# Rotall_Encoder_ver1_0.net
KiCad netlist of a schematic drawn in EAGLE
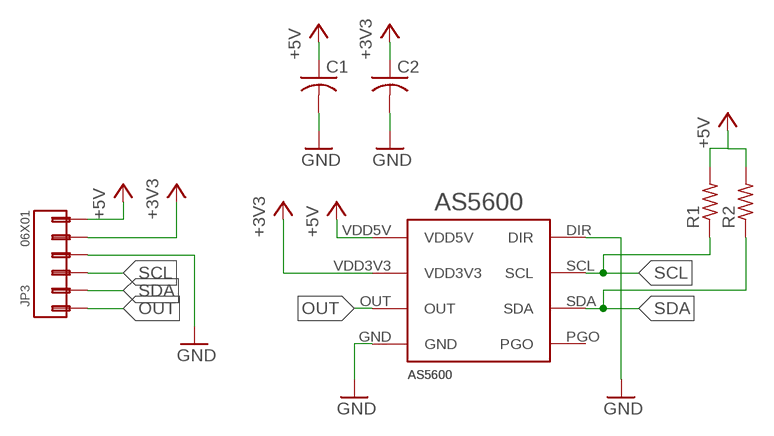
[diagram p0: schematic, sheet 1]

(export (version "E")
  (design (tool "Eeschema 10.0.6"))
  (components
    (comp (ref "C1")
      (value "C-USC0603")
      (footprint "eagle-import:C0603")
      (libsource (lib "eagle-import") (part "C-USC0603"))
    )
    (comp (ref "C2")
      (value "C-USC0603")
      (footprint "eagle-import:C0603")
      (libsource (lib "eagle-import") (part "C-USC0603"))
    )
    (comp (ref "JP3")
      (value "06X01")
      (footprint "eagle-import:06X01")
      (libsource (lib "eagle-import") (part "06X01"))
    )
    (comp (ref "R1")
      (value "R-US_R0603")
      (footprint "eagle-import:R0603")
      (libsource (lib "eagle-import") (part "R-US_R0603"))
    )
    (comp (ref "R2")
      (value "R-US_R0603")
      (footprint "eagle-import:R0603")
      (libsource (lib "eagle-import") (part "R-US_R0603"))
    )
    (comp (ref "U1")
      (value "AS5600")
      (footprint "eagle-import:AS5600")
      (libsource (lib "eagle-import") (part "AS5600"))
    )
  )
  (nets
    (net (code "1") (name "+3V3") (class "Default")
      (node (ref "C2") (pin "1") (pinfunction "1_1") (pintype "passive"))
      (node (ref "JP3") (pin "2") (pinfunction "2_2") (pintype "bidirectional"))
      (node (ref "U1") (pin "VDD3V3") (pinfunction "VDD3V3_VDD3V3") (pintype "bidirectional"))
    )
    (net (code "2") (name "+5V") (class "Default")
      (node (ref "C1") (pin "1") (pinfunction "1_1") (pintype "passive"))
      (node (ref "JP3") (pin "1") (pinfunction "1_1") (pintype "bidirectional"))
      (node (ref "R1") (pin "2") (pinfunction "2_2") (pintype "passive"))
      (node (ref "R2") (pin "2") (pinfunction "2_2") (pintype "passive"))
      (node (ref "U1") (pin "VDD5V") (pinfunction "VDD5V_VDD5V") (pintype "bidirectional"))
    )
    (net (code "3") (name "GND") (class "Default")
      (node (ref "C1") (pin "2") (pinfunction "2_2") (pintype "passive"))
      (node (ref "C2") (pin "2") (pinfunction "2_2") (pintype "passive"))
      (node (ref "JP3") (pin "3") (pinfunction "3_3") (pintype "bidirectional"))
      (node (ref "U1") (pin "DIR") (pinfunction "DIR_DIR") (pintype "bidirectional"))
      (node (ref "U1") (pin "GND") (pinfunction "GND_GND") (pintype "bidirectional"))
    )
    (net (code "4") (name "OUT") (class "Default")
      (node (ref "JP3") (pin "6") (pinfunction "6_6") (pintype "bidirectional"))
      (node (ref "U1") (pin "OUT") (pinfunction "OUT_OUT") (pintype "bidirectional"))
    )
    (net (code "5") (name "SCL") (class "Default")
      (node (ref "JP3") (pin "4") (pinfunction "4_4") (pintype "bidirectional"))
      (node (ref "R1") (pin "1") (pinfunction "1_1") (pintype "passive"))
      (node (ref "U1") (pin "SCL") (pinfunction "SCL_SCL") (pintype "bidirectional"))
    )
    (net (code "6") (name "SDA") (class "Default")
      (node (ref "JP3") (pin "5") (pinfunction "5_5") (pintype "bidirectional"))
      (node (ref "R2") (pin "1") (pinfunction "1_1") (pintype "passive"))
      (node (ref "U1") (pin "SDA") (pinfunction "SDA_SDA") (pintype "bidirectional"))
    )
    (net (code "7") (name "unconnected-(U1-PadPGO)") (class "Default")
      (node (ref "U1") (pin "PGO") (pinfunction "PGO_PGO") (pintype "bidirectional"))
    )
  )
)
